# BL8028.net
KiCad netlist of a schematic drawn in Altium Designer
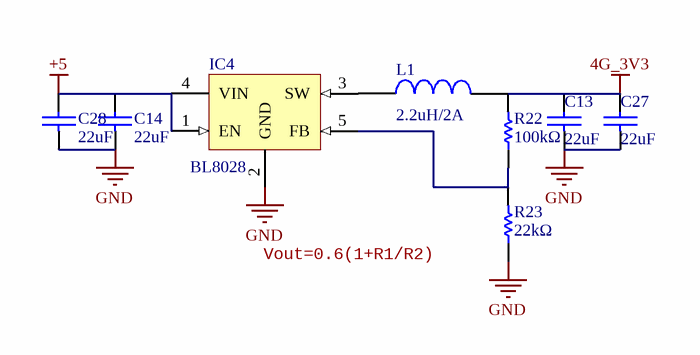
[diagram p0: BL8028.SchDoc]

(export (version "E")
  (design (tool "Eeschema 10.0.6"))
  (components
    (comp (ref "C13")
      (value "22uF")
      (footprint "C_0603")
      (description "贴片电容")
      (libsource (lib "IntLib-Passive") (part "Cap_Chip"))
    )
    (comp (ref "C14")
      (value "22uF")
      (footprint "C_0603")
      (description "贴片电容")
      (libsource (lib "IntLib-Passive") (part "Cap_Chip"))
    )
    (comp (ref "C27")
      (value "22uF")
      (footprint "C_0603")
      (description "贴片电容")
      (libsource (lib "IntLib-Passive") (part "Cap_Chip"))
    )
    (comp (ref "C28")
      (value "22uF")
      (footprint "C_0603")
      (description "贴片电容")
      (libsource (lib "IntLib-Passive") (part "Cap_Chip"))
    )
    (comp (ref "IC4")
      (value "BL8028")
      (footprint "SOT23-5")
      (description "DC-DC 芯片")
      (fields (field (name "MANUFACTURER_PART_NUMBER") "BL8028CB5TR"))
      (libsource (lib "IntLib-IC") (part "BL8028"))
    )
    (comp (ref "L1")
      (value "2.2uH/2A")
      (footprint "L_1008")
      (description "小功率电感")
      (fields (field (name "MANUFACTURER_PART_NUMBER") "BDCD002520122R2MS1"))
      (libsource (lib "IntLib-Passive") (part "Ind_Chip"))
    )
    (comp (ref "R22")
      (value "100kΩ")
      (footprint "R_0402")
      (description "贴片电阻")
      (libsource (lib "IntLib-Passive") (part "Res_Chip"))
    )
    (comp (ref "R23")
      (value "22kΩ")
      (footprint "R_0402")
      (description "贴片电阻")
      (libsource (lib "IntLib-Passive") (part "Res_Chip"))
    )
  )
  (nets
    (net (code "1") (name "+5") (class "Default")
      (node (ref "C14") (pin "2") (pinfunction "2_2") (pintype "passive"))
      (node (ref "C28") (pin "2") (pinfunction "2_2") (pintype "passive"))
      (node (ref "IC4") (pin "1") (pinfunction "EN_1") (pintype "input"))
      (node (ref "IC4") (pin "4") (pinfunction "VIN_4") (pintype "power_in"))
    )
    (net (code "2") (name "4G_3V3") (class "Default")
      (node (ref "C13") (pin "2") (pinfunction "2_2") (pintype "passive"))
      (node (ref "C27") (pin "2") (pinfunction "2_2") (pintype "passive"))
      (node (ref "L1") (pin "2") (pinfunction "2_2") (pintype "passive"))
      (node (ref "R22") (pin "2") (pinfunction "2_2") (pintype "passive"))
    )
    (net (code "3") (name "GND") (class "Default")
      (node (ref "C13") (pin "1") (pinfunction "1_1") (pintype "passive"))
      (node (ref "C14") (pin "1") (pinfunction "1_1") (pintype "passive"))
      (node (ref "C27") (pin "1") (pinfunction "1_1") (pintype "passive"))
      (node (ref "C28") (pin "1") (pinfunction "1_1") (pintype "passive"))
      (node (ref "IC4") (pin "2") (pinfunction "GND_2") (pintype "power_in"))
      (node (ref "R23") (pin "1") (pinfunction "1_1") (pintype "passive"))
    )
    (net (code "4") (name "Net-(IC4-FB)") (class "Default")
      (node (ref "IC4") (pin "5") (pinfunction "FB_5") (pintype "input"))
      (node (ref "R22") (pin "1") (pinfunction "1_1") (pintype "passive"))
      (node (ref "R23") (pin "2") (pinfunction "2_2") (pintype "passive"))
    )
    (net (code "5") (name "Net-(IC4-SW)") (class "Default")
      (node (ref "IC4") (pin "3") (pinfunction "SW_3") (pintype "input"))
      (node (ref "L1") (pin "1") (pinfunction "1_1") (pintype "passive"))
    )
  )
)
